# rfid.net
KiCad netlist of a schematic drawn in EAGLE
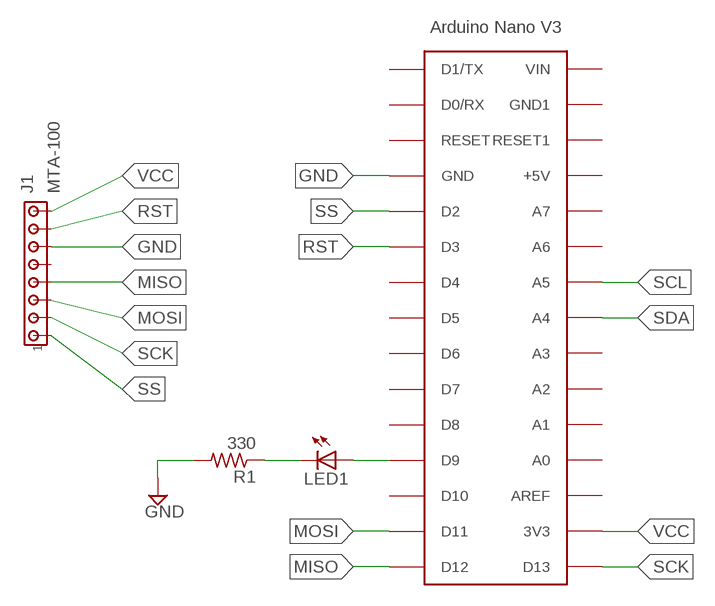
[diagram p0: schematic, sheet 1]

(export (version "E")
  (design (tool "Eeschema 10.0.6"))
  (components
    (comp (ref "J1")
      (value "MTA-100")
      (footprint "eagle-import:10X08MTA")
      (libsource (lib "eagle-import") (part "MTA08-100"))
    )
    (comp (ref "LED1")
      (value "LED5MM")
      (footprint "eagle-import:LED5MM")
      (libsource (lib "eagle-import") (part "LED5MM"))
    )
    (comp (ref "R1")
      (value "330")
      (footprint "eagle-import:0207_10")
      (libsource (lib "eagle-import") (part "R-US_0207/10"))
    )
    (comp (ref "U$1")
      (value "ARDUINONANO")
      (footprint "eagle-import:PDIP-32")
      (libsource (lib "eagle-import") (part "ARDUINONANO"))
    )
  )
  (nets
    (net (code "1") (name "GND") (class "Default")
      (node (ref "J1") (pin "6") (pinfunction "6_6") (pintype "passive"))
      (node (ref "R1") (pin "2") (pinfunction "2_2") (pintype "passive"))
      (node (ref "U$1") (pin "GND") (pinfunction "GND_GND") (pintype "bidirectional"))
    )
    (net (code "2") (name "MISO") (class "Default")
      (node (ref "J1") (pin "4") (pinfunction "4_4") (pintype "passive"))
      (node (ref "U$1") (pin "D12") (pinfunction "D12_D12") (pintype "bidirectional"))
    )
    (net (code "3") (name "MOSI") (class "Default")
      (node (ref "J1") (pin "3") (pinfunction "3_3") (pintype "passive"))
      (node (ref "U$1") (pin "D11") (pinfunction "D11_D11") (pintype "bidirectional"))
    )
    (net (code "4") (name "Net-(LED1-C)") (class "Default")
      (node (ref "LED1") (pin "K") (pinfunction "C_K") (pintype "passive"))
      (node (ref "R1") (pin "1") (pinfunction "1_1") (pintype "passive"))
    )
    (net (code "5") (name "Net-(LED1-PadA)") (class "Default")
      (node (ref "LED1") (pin "A") (pinfunction "A_A") (pintype "passive"))
      (node (ref "U$1") (pin "D9") (pinfunction "D9_D9") (pintype "bidirectional"))
    )
    (net (code "6") (name "RST") (class "Default")
      (node (ref "J1") (pin "7") (pinfunction "7_7") (pintype "passive"))
      (node (ref "U$1") (pin "D3") (pinfunction "D3_D3") (pintype "bidirectional"))
    )
    (net (code "7") (name "SCK") (class "Default")
      (node (ref "J1") (pin "2") (pinfunction "2_2") (pintype "passive"))
      (node (ref "U$1") (pin "D13") (pinfunction "D13_D13") (pintype "bidirectional"))
    )
    (net (code "8") (name "SCL") (class "Default")
      (node (ref "U$1") (pin "A2") (pinfunction "A5_A2") (pintype "bidirectional"))
    )
    (net (code "9") (name "SDA") (class "Default")
      (node (ref "U$1") (pin "A3") (pinfunction "A4_A3") (pintype "bidirectional"))
    )
    (net (code "10") (name "SS") (class "Default")
      (node (ref "J1") (pin "1") (pinfunction "1_1") (pintype "passive"))
      (node (ref "U$1") (pin "D2") (pinfunction "D2_D2") (pintype "bidirectional"))
    )
    (net (code "11") (name "VCC") (class "Default")
      (node (ref "J1") (pin "8") (pinfunction "8_8") (pintype "passive"))
      (node (ref "U$1") (pin "3V3") (pinfunction "3V3_3V3") (pintype "bidirectional"))
    )
    (net (code "12") (name "unconnected-(J1-Pad5)") (class "Default")
      (node (ref "J1") (pin "5") (pinfunction "5_5") (pintype "passive"))
    )
    (net (code "13") (name "unconnected-(U$1-A0-PadA7)") (class "Default")
      (node (ref "U$1") (pin "A7") (pinfunction "A0_A7") (pintype "bidirectional"))
    )
    (net (code "14") (name "unconnected-(U$1-A1-PadA6)") (class "Default")
      (node (ref "U$1") (pin "A6") (pinfunction "A1_A6") (pintype "bidirectional"))
    )
    (net (code "15") (name "unconnected-(U$1-A2-PadA5)") (class "Default")
      (node (ref "U$1") (pin "A5") (pinfunction "A2_A5") (pintype "bidirectional"))
    )
    (net (code "16") (name "unconnected-(U$1-A3-PadA4)") (class "Default")
      (node (ref "U$1") (pin "A4") (pinfunction "A3_A4") (pintype "bidirectional"))
    )
    (net (code "17") (name "unconnected-(U$1-A6-PadA1)") (class "Default")
      (node (ref "U$1") (pin "A1") (pinfunction "A6_A1") (pintype "bidirectional"))
    )
    (net (code "18") (name "unconnected-(U$1-A7-PadA0)") (class "Default")
      (node (ref "U$1") (pin "A0") (pinfunction "A7_A0") (pintype "bidirectional"))
    )
    (net (code "19") (name "unconnected-(U$1-Pad+5V)") (class "Default")
      (node (ref "U$1") (pin "+5V") (pinfunction "+5V_+5V") (pintype "bidirectional"))
    )
    (net (code "20") (name "unconnected-(U$1-PadAREF)") (class "Default")
      (node (ref "U$1") (pin "AREF") (pinfunction "AREF_AREF") (pintype "bidirectional"))
    )
    (net (code "21") (name "unconnected-(U$1-PadD0{slash}RX)") (class "Default")
      (node (ref "U$1") (pin "D0/RX") (pinfunction "D0/RX_D0/RX") (pintype "bidirectional"))
    )
    (net (code "22") (name "unconnected-(U$1-PadD1{slash}TX)") (class "Default")
      (node (ref "U$1") (pin "D1/TX") (pinfunction "D1/TX_D1/TX") (pintype "bidirectional"))
    )
    (net (code "23") (name "unconnected-(U$1-PadD4)") (class "Default")
      (node (ref "U$1") (pin "D4") (pinfunction "D4_D4") (pintype "bidirectional"))
    )
    (net (code "24") (name "unconnected-(U$1-PadD5)") (class "Default")
      (node (ref "U$1") (pin "D5") (pinfunction "D5_D5") (pintype "bidirectional"))
    )
    (net (code "25") (name "unconnected-(U$1-PadD6)") (class "Default")
      (node (ref "U$1") (pin "D6") (pinfunction "D6_D6") (pintype "bidirectional"))
    )
    (net (code "26") (name "unconnected-(U$1-PadD7)") (class "Default")
      (node (ref "U$1") (pin "D7") (pinfunction "D7_D7") (pintype "bidirectional"))
    )
    (net (code "27") (name "unconnected-(U$1-PadD8)") (class "Default")
      (node (ref "U$1") (pin "D8") (pinfunction "D8_D8") (pintype "bidirectional"))
    )
    (net (code "28") (name "unconnected-(U$1-PadD10)") (class "Default")
      (node (ref "U$1") (pin "D10") (pinfunction "D10_D10") (pintype "bidirectional"))
    )
    (net (code "29") (name "unconnected-(U$1-PadGND1)") (class "Default")
      (node (ref "U$1") (pin "GND1") (pinfunction "GND1_GND1") (pintype "bidirectional"))
    )
    (net (code "30") (name "unconnected-(U$1-PadRESET)") (class "Default")
      (node (ref "U$1") (pin "RESET") (pinfunction "RESET_RESET") (pintype "bidirectional"))
    )
    (net (code "31") (name "unconnected-(U$1-PadRESET1)") (class "Default")
      (node (ref "U$1") (pin "RESET1") (pinfunction "RESET1_RESET1") (pintype "bidirectional"))
    )
    (net (code "32") (name "unconnected-(U$1-PadVIN)") (class "Default")
      (node (ref "U$1") (pin "VIN") (pinfunction "VIN_VIN") (pintype "bidirectional"))
    )
  )
)
